# supply_test_2v1.net
KiCad netlist of a schematic drawn in EAGLE
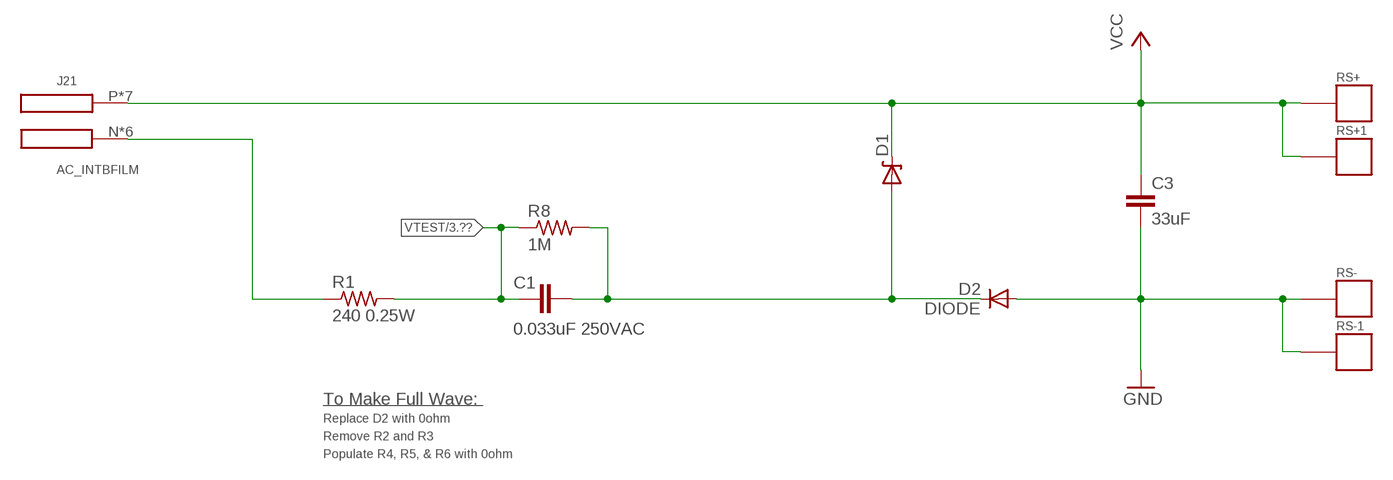
[diagram p0: schematic, sheet 1]
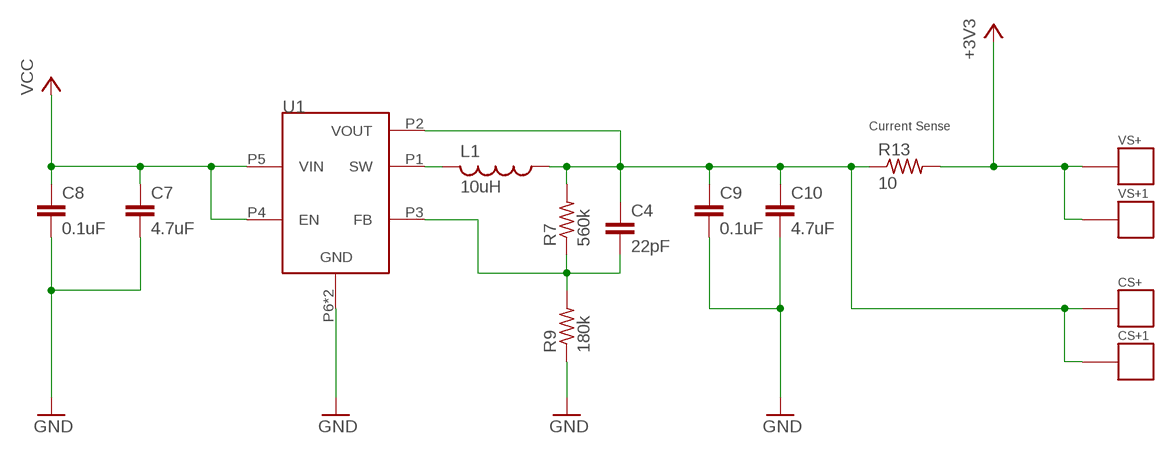
[diagram p1: schematic, sheet 2]
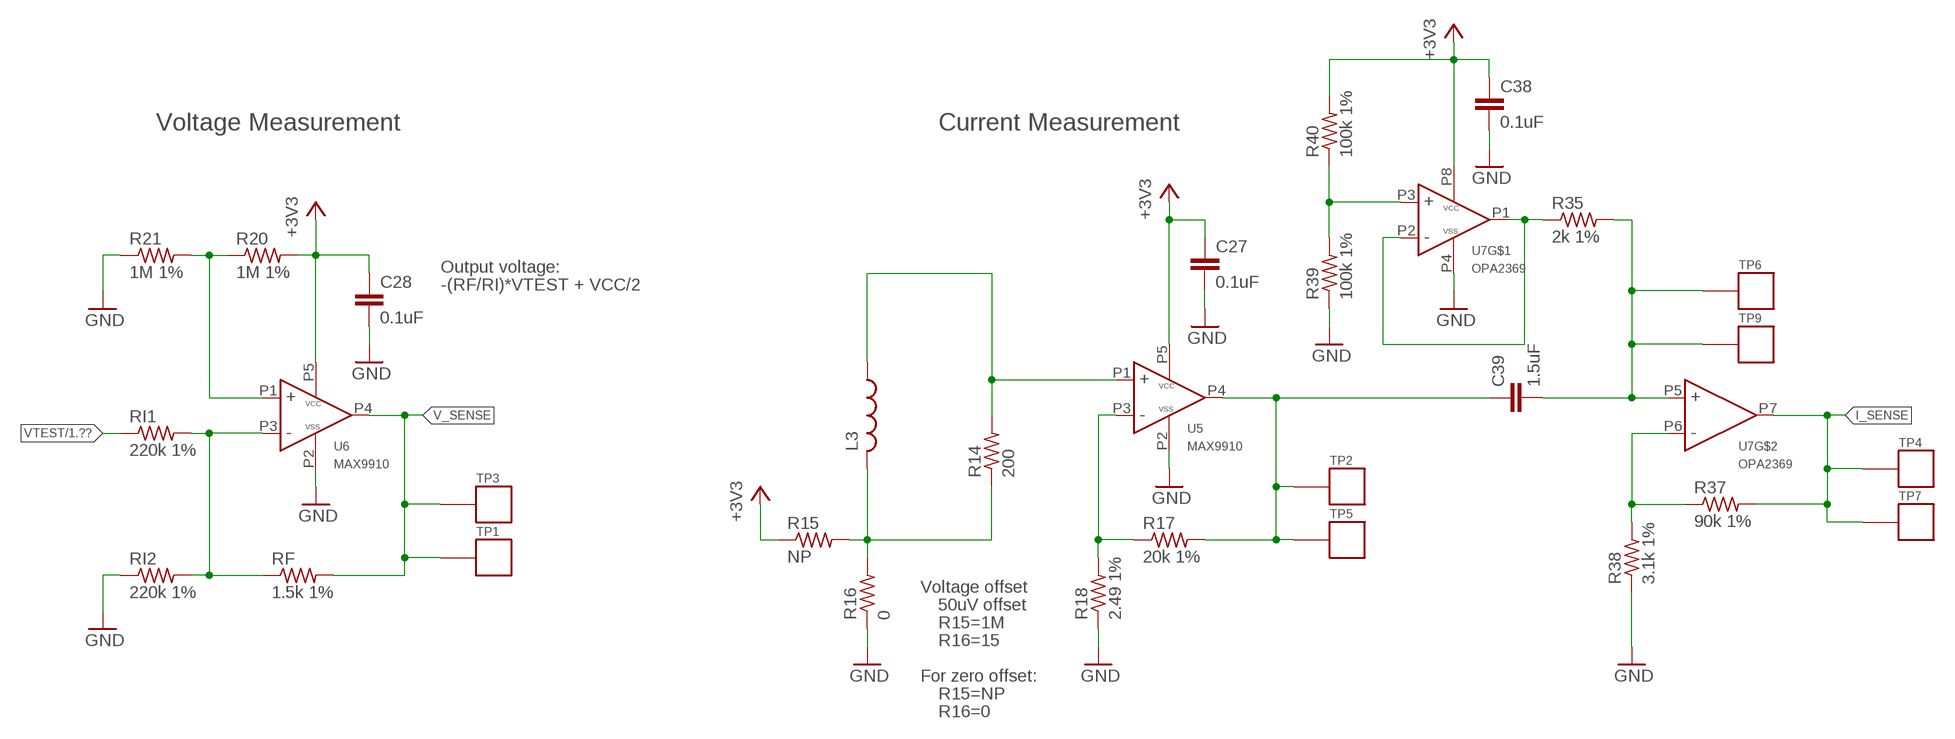
[diagram p2: schematic, sheet 3]

(export (version "E")
  (design (tool "Eeschema 10.0.6"))
  (components
    (comp (ref "C4")
      (value "22pF")
      (footprint "eagle-import:C0402")
      (libsource (lib "eagle-import") (part "C-EUC0402"))
    )
    (comp (ref "C7")
      (value "4.7uF")
      (footprint "eagle-import:C0402")
      (libsource (lib "eagle-import") (part "C-EUC0402"))
    )
    (comp (ref "C8")
      (value "0.1uF")
      (footprint "eagle-import:C0402")
      (libsource (lib "eagle-import") (part "C-EUC0402"))
    )
    (comp (ref "C9")
      (value "0.1uF")
      (footprint "eagle-import:C0402")
      (libsource (lib "eagle-import") (part "C-EUC0402"))
    )
    (comp (ref "C10")
      (value "4.7uF")
      (footprint "eagle-import:C0603")
      (libsource (lib "eagle-import") (part "C-EUC0603"))
    )
    (comp (ref "CS+")
      (value "TP_LONG")
      (footprint "eagle-import:TP_LONG")
      (libsource (lib "eagle-import") (part "TP_LONG"))
    )
    (comp (ref "CS+1")
      (value "TP_SMD")
      (footprint "eagle-import:TP_SMD")
      (libsource (lib "eagle-import") (part "TP_SMD"))
    )
    (comp (ref "L1")
      (value "10uH")
      (footprint "eagle-import:L0805")
      (libsource (lib "eagle-import") (part "L-USL0805"))
    )
    (comp (ref "R7")
      (value "560k")
      (footprint "eagle-import:R0402")
      (libsource (lib "eagle-import") (part "R-US_R0402"))
    )
    (comp (ref "R9")
      (value "180k")
      (footprint "eagle-import:R0402")
      (libsource (lib "eagle-import") (part "R-US_R0402"))
    )
    (comp (ref "R13")
      (value "10")
      (footprint "eagle-import:R0603")
      (libsource (lib "eagle-import") (part "R-US_R0603"))
    )
    (comp (ref "U1")
      (value "TPS62122")
      (footprint "eagle-import:WDFN-6")
      (libsource (lib "eagle-import") (part "TPS62122"))
    )
    (comp (ref "VS+")
      (value "TP_LONG")
      (footprint "eagle-import:TP_LONG")
      (libsource (lib "eagle-import") (part "TP_LONG"))
    )
    (comp (ref "VS+1")
      (value "TP_SMD")
      (footprint "eagle-import:TP_SMD")
      (libsource (lib "eagle-import") (part "TP_SMD"))
    )
    (comp (ref "C27")
      (value "0.1uF")
      (footprint "eagle-import:C0402")
      (libsource (lib "eagle-import") (part "C-EUC0402"))
    )
    (comp (ref "C28")
      (value "0.1uF")
      (footprint "eagle-import:C0402")
      (libsource (lib "eagle-import") (part "C-EUC0402"))
    )
    (comp (ref "C38")
      (value "0.1uF")
      (footprint "eagle-import:C0402")
      (libsource (lib "eagle-import") (part "C-EUC0402"))
    )
    (comp (ref "C39")
      (value "1.5uF")
      (footprint "eagle-import:C0402")
      (libsource (lib "eagle-import") (part "C-EUC0402"))
    )
    (comp (ref "L3")
      (value "L-USL0805")
      (footprint "eagle-import:L0805")
      (libsource (lib "eagle-import") (part "L-USL0805"))
    )
    (comp (ref "R14")
      (value "200")
      (footprint "eagle-import:R0402")
      (libsource (lib "eagle-import") (part "R-US_R0402"))
    )
    (comp (ref "R15")
      (value "NP")
      (footprint "eagle-import:R0402")
      (libsource (lib "eagle-import") (part "R-US_R0402"))
    )
    (comp (ref "R16")
      (value "0")
      (footprint "eagle-import:R0402")
      (libsource (lib "eagle-import") (part "R-US_R0402"))
    )
    (comp (ref "R17")
      (value "20k 1%")
      (footprint "eagle-import:R0402")
      (libsource (lib "eagle-import") (part "R-US_R0402"))
    )
    (comp (ref "R18")
      (value "2.49 1%")
      (footprint "eagle-import:R0402")
      (libsource (lib "eagle-import") (part "R-US_R0402"))
    )
    (comp (ref "R20")
      (value "1M 1%")
      (footprint "eagle-import:R0402")
      (libsource (lib "eagle-import") (part "R-US_R0402"))
    )
    (comp (ref "R21")
      (value "1M 1%")
      (footprint "eagle-import:R0402")
      (libsource (lib "eagle-import") (part "R-US_R0402"))
    )
    (comp (ref "R35")
      (value "2k 1%")
      (footprint "eagle-import:R0402")
      (libsource (lib "eagle-import") (part "R-US_R0402"))
    )
    (comp (ref "R37")
      (value "90k 1%")
      (footprint "eagle-import:R0402")
      (libsource (lib "eagle-import") (part "R-US_R0402"))
    )
    (comp (ref "R38")
      (value "3.1k 1%")
      (footprint "eagle-import:R0402")
      (libsource (lib "eagle-import") (part "R-US_R0402"))
    )
    (comp (ref "R39")
      (value "100k 1%")
      (footprint "eagle-import:R0402")
      (libsource (lib "eagle-import") (part "R-US_R0402"))
    )
    (comp (ref "R40")
      (value "100k 1%")
      (footprint "eagle-import:R0402")
      (libsource (lib "eagle-import") (part "R-US_R0402"))
    )
    (comp (ref "RF")
      (value "1.5k 1%")
      (footprint "eagle-import:R0402")
      (libsource (lib "eagle-import") (part "R-US_R0402"))
    )
    (comp (ref "RI1")
      (value "220k 1%")
      (footprint "eagle-import:R0402")
      (libsource (lib "eagle-import") (part "R-US_R0402"))
    )
    (comp (ref "RI2")
      (value "220k 1%")
      (footprint "eagle-import:R0402")
      (libsource (lib "eagle-import") (part "R-US_R0402"))
    )
    (comp (ref "TP1")
      (value "TP_SMD")
      (footprint "eagle-import:TP_SMD")
      (libsource (lib "eagle-import") (part "TP_SMD"))
    )
    (comp (ref "TP2")
      (value "TP_LONG")
      (footprint "eagle-import:TP_LONG")
      (libsource (lib "eagle-import") (part "TP_LONG"))
    )
    (comp (ref "TP3")
      (value "TP_LONG")
      (footprint "eagle-import:TP_LONG")
      (libsource (lib "eagle-import") (part "TP_LONG"))
    )
    (comp (ref "TP4")
      (value "TP_LONG")
      (footprint "eagle-import:TP_LONG")
      (libsource (lib "eagle-import") (part "TP_LONG"))
    )
    (comp (ref "TP5")
      (value "TP_SMD")
      (footprint "eagle-import:TP_SMD")
      (libsource (lib "eagle-import") (part "TP_SMD"))
    )
    (comp (ref "TP6")
      (value "TP_SMD")
      (footprint "eagle-import:TP_SMD")
      (libsource (lib "eagle-import") (part "TP_SMD"))
    )
    (comp (ref "TP7")
      (value "TP_SMD")
      (footprint "eagle-import:TP_SMD")
      (libsource (lib "eagle-import") (part "TP_SMD"))
    )
    (comp (ref "TP9")
      (value "TP_LONG")
      (footprint "eagle-import:TP_LONG")
      (libsource (lib "eagle-import") (part "TP_LONG"))
    )
    (comp (ref "U5")
      (value "MAX9910")
      (footprint "eagle-import:SC70-5")
      (libsource (lib "eagle-import") (part "MAX9910"))
    )
    (comp (ref "U6")
      (value "MAX9910")
      (footprint "eagle-import:SC70-5")
      (libsource (lib "eagle-import") (part "MAX9910"))
    )
    (comp (ref "U7")
      (value "OPA2369")
      (footprint "eagle-import:SOT-23-8")
      (libsource (lib "eagle-import") (part "OPA2369"))
    )
    (comp (ref "C1")
      (value "0.033uF 250VAC")
      (footprint "eagle-import:C2220-EDGE")
      (libsource (lib "eagle-import") (part "C-EUEDGE"))
    )
    (comp (ref "C3")
      (value "33uF")
      (footprint "eagle-import:C0603")
      (libsource (lib "eagle-import") (part "C-EUC0603"))
    )
    (comp (ref "D1")
      (value "ZENERBZT52")
      (footprint "eagle-import:BZT52")
      (fields (field (name "DIGIKEY") "BZT52C10T-7DICT-ND "))
      (libsource (lib "eagle-import") (part "ZENERBZT52"))
    )
    (comp (ref "D2")
      (value "DIODE")
      (footprint "eagle-import:BAS521")
      (libsource (lib "eagle-import") (part "DIODE"))
    )
    (comp (ref "J21")
      (value "AC_INTBFILM")
      (footprint "eagle-import:AC3_TBFILM")
      (libsource (lib "eagle-import") (part "AC_INTBFILM"))
    )
    (comp (ref "R1")
      (value "240 0.25W")
      (footprint "eagle-import:R0603")
      (libsource (lib "eagle-import") (part "R-US_R0603"))
    )
    (comp (ref "R8")
      (value "1M")
      (footprint "eagle-import:R0603")
      (libsource (lib "eagle-import") (part "R-US_R0603"))
    )
    (comp (ref "RS+")
      (value "TP_LONG")
      (footprint "eagle-import:TP_LONG")
      (libsource (lib "eagle-import") (part "TP_LONG"))
    )
    (comp (ref "RS+1")
      (value "TP_SMD")
      (footprint "eagle-import:TP_SMD")
      (libsource (lib "eagle-import") (part "TP_SMD"))
    )
    (comp (ref "RS-")
      (value "TP_LONG")
      (footprint "eagle-import:TP_LONG")
      (libsource (lib "eagle-import") (part "TP_LONG"))
    )
    (comp (ref "RS-1")
      (value "TP_SMD")
      (footprint "eagle-import:TP_SMD")
      (libsource (lib "eagle-import") (part "TP_SMD"))
    )
  )
  (nets
    (net (code "1") (name "+3V3") (class "Default")
      (node (ref "C27") (pin "1") (pinfunction "1_1") (pintype "passive"))
      (node (ref "C28") (pin "1") (pinfunction "1_1") (pintype "passive"))
      (node (ref "C38") (pin "1") (pinfunction "1_1") (pintype "passive"))
      (node (ref "R13") (pin "2") (pinfunction "2_2") (pintype "passive"))
      (node (ref "R15") (pin "1") (pinfunction "1_1") (pintype "passive"))
      (node (ref "R20") (pin "2") (pinfunction "2_2") (pintype "passive"))
      (node (ref "R40") (pin "2") (pinfunction "2_2") (pintype "passive"))
      (node (ref "U5") (pin "P5") (pinfunction "VCC_P5") (pintype "bidirectional"))
      (node (ref "U6") (pin "P5") (pinfunction "VCC_P5") (pintype "bidirectional"))
      (node (ref "U7") (pin "P8") (pinfunction "VCC_P8") (pintype "bidirectional"))
      (node (ref "VS+") (pin "P$1") (pinfunction "P$1_P$1") (pintype "bidirectional"))
      (node (ref "VS+1") (pin "P$1") (pinfunction "P$1_P$1") (pintype "bidirectional"))
    )
    (net (code "2") (name "GND") (class "Default")
      (node (ref "C10") (pin "2") (pinfunction "2_2") (pintype "passive"))
      (node (ref "C27") (pin "2") (pinfunction "2_2") (pintype "passive"))
      (node (ref "C28") (pin "2") (pinfunction "2_2") (pintype "passive"))
      (node (ref "C3") (pin "2") (pinfunction "2_2") (pintype "passive"))
      (node (ref "C38") (pin "2") (pinfunction "2_2") (pintype "passive"))
      (node (ref "C7") (pin "2") (pinfunction "2_2") (pintype "passive"))
      (node (ref "C8") (pin "2") (pinfunction "2_2") (pintype "passive"))
      (node (ref "C9") (pin "2") (pinfunction "2_2") (pintype "passive"))
      (node (ref "D2") (pin "A") (pinfunction "A_A") (pintype "passive"))
      (node (ref "R16") (pin "1") (pinfunction "1_1") (pintype "passive"))
      (node (ref "R18") (pin "1") (pinfunction "1_1") (pintype "passive"))
      (node (ref "R21") (pin "1") (pinfunction "1_1") (pintype "passive"))
      (node (ref "R38") (pin "1") (pinfunction "1_1") (pintype "passive"))
      (node (ref "R39") (pin "1") (pinfunction "1_1") (pintype "passive"))
      (node (ref "R9") (pin "1") (pinfunction "1_1") (pintype "passive"))
      (node (ref "RI2") (pin "1") (pinfunction "1_1") (pintype "passive"))
      (node (ref "RS-") (pin "P$1") (pinfunction "P$1_P$1") (pintype "bidirectional"))
      (node (ref "RS-1") (pin "P$1") (pinfunction "P$1_P$1") (pintype "bidirectional"))
      (node (ref "U1") (pin "P6") (pinfunction "GND_P6") (pintype "bidirectional"))
      (node (ref "U1") (pin "PAD") (pinfunction "GND_PAD") (pintype "bidirectional"))
      (node (ref "U5") (pin "P2") (pinfunction "VSS_P2") (pintype "bidirectional"))
      (node (ref "U6") (pin "P2") (pinfunction "VSS_P2") (pintype "bidirectional"))
      (node (ref "U7") (pin "P4") (pinfunction "VSS_P4") (pintype "bidirectional"))
    )
    (net (code "3") (name "I_SENSE") (class "Default")
      (node (ref "R37") (pin "2") (pinfunction "2_2") (pintype "passive"))
      (node (ref "TP4") (pin "P$1") (pinfunction "P$1_P$1") (pintype "bidirectional"))
      (node (ref "TP7") (pin "P$1") (pinfunction "P$1_P$1") (pintype "bidirectional"))
      (node (ref "U7") (pin "P7") (pinfunction "OUT_P7") (pintype "bidirectional"))
    )
    (net (code "4") (name "Net-(C1-Pad1)") (class "Default")
      (node (ref "C1") (pin "1") (pinfunction "1_1") (pintype "passive"))
      (node (ref "D1") (pin "A") (pinfunction "A_A") (pintype "passive"))
      (node (ref "D2") (pin "C") (pinfunction "C_C") (pintype "passive"))
      (node (ref "R8") (pin "2") (pinfunction "2_2") (pintype "passive"))
    )
    (net (code "5") (name "Net-(J21-N-PadN1)") (class "Default")
      (node (ref "J21") (pin "N") (pinfunction "N_N") (pintype "bidirectional"))
      (node (ref "J21") (pin "N1") (pinfunction "N_N1") (pintype "bidirectional"))
      (node (ref "J21") (pin "N2") (pinfunction "N_N2") (pintype "bidirectional"))
      (node (ref "J21") (pin "N3") (pinfunction "N_N3") (pintype "bidirectional"))
      (node (ref "J21") (pin "N4") (pinfunction "N_N4") (pintype "bidirectional"))
      (node (ref "J21") (pin "N5") (pinfunction "N_N5") (pintype "bidirectional"))
      (node (ref "R1") (pin "1") (pinfunction "1_1") (pintype "passive"))
    )
    (net (code "6") (name "Net-(L3-Pad2)") (class "Default")
      (node (ref "L3") (pin "2") (pinfunction "2_2") (pintype "passive"))
      (node (ref "R14") (pin "1") (pinfunction "1_1") (pintype "passive"))
      (node (ref "R15") (pin "2") (pinfunction "2_2") (pintype "passive"))
      (node (ref "R16") (pin "2") (pinfunction "2_2") (pintype "passive"))
    )
    (net (code "7") (name "Net-(U1-FB)") (class "Default")
      (node (ref "C4") (pin "2") (pinfunction "2_2") (pintype "passive"))
      (node (ref "R7") (pin "1") (pinfunction "1_1") (pintype "passive"))
      (node (ref "R9") (pin "2") (pinfunction "2_2") (pintype "passive"))
      (node (ref "U1") (pin "P3") (pinfunction "FB_P3") (pintype "bidirectional"))
    )
    (net (code "8") (name "Net-(U1-SW)") (class "Default")
      (node (ref "L1") (pin "2") (pinfunction "2_2") (pintype "passive"))
      (node (ref "U1") (pin "P1") (pinfunction "SW_P1") (pintype "bidirectional"))
    )
    (net (code "9") (name "Net-(U1-VOUT)") (class "Default")
      (node (ref "C10") (pin "1") (pinfunction "1_1") (pintype "passive"))
      (node (ref "C4") (pin "1") (pinfunction "1_1") (pintype "passive"))
      (node (ref "C9") (pin "1") (pinfunction "1_1") (pintype "passive"))
      (node (ref "CS+") (pin "P$1") (pinfunction "P$1_P$1") (pintype "bidirectional"))
      (node (ref "CS+1") (pin "P$1") (pinfunction "P$1_P$1") (pintype "bidirectional"))
      (node (ref "L1") (pin "1") (pinfunction "1_1") (pintype "passive"))
      (node (ref "R13") (pin "1") (pinfunction "1_1") (pintype "passive"))
      (node (ref "R7") (pin "2") (pinfunction "2_2") (pintype "passive"))
      (node (ref "U1") (pin "P2") (pinfunction "VOUT_P2") (pintype "bidirectional"))
    )
    (net (code "10") (name "Net-(U5-IN+)") (class "Default")
      (node (ref "L3") (pin "1") (pinfunction "1_1") (pintype "passive"))
      (node (ref "R14") (pin "2") (pinfunction "2_2") (pintype "passive"))
      (node (ref "U5") (pin "P1") (pinfunction "IN+_P1") (pintype "bidirectional"))
    )
    (net (code "11") (name "Net-(U5-IN-)") (class "Default")
      (node (ref "R17") (pin "1") (pinfunction "1_1") (pintype "passive"))
      (node (ref "R18") (pin "2") (pinfunction "2_2") (pintype "passive"))
      (node (ref "U5") (pin "P3") (pinfunction "IN-_P3") (pintype "bidirectional"))
    )
    (net (code "12") (name "Net-(U5-OUT)") (class "Default")
      (node (ref "C39") (pin "1") (pinfunction "1_1") (pintype "passive"))
      (node (ref "R17") (pin "2") (pinfunction "2_2") (pintype "passive"))
      (node (ref "TP2") (pin "P$1") (pinfunction "P$1_P$1") (pintype "bidirectional"))
      (node (ref "TP5") (pin "P$1") (pinfunction "P$1_P$1") (pintype "bidirectional"))
      (node (ref "U5") (pin "P4") (pinfunction "OUT_P4") (pintype "bidirectional"))
    )
    (net (code "13") (name "Net-(U6-IN+)") (class "Default")
      (node (ref "R20") (pin "1") (pinfunction "1_1") (pintype "passive"))
      (node (ref "R21") (pin "2") (pinfunction "2_2") (pintype "passive"))
      (node (ref "U6") (pin "P1") (pinfunction "IN+_P1") (pintype "bidirectional"))
    )
    (net (code "14") (name "Net-(U6-IN-)") (class "Default")
      (node (ref "RF") (pin "1") (pinfunction "1_1") (pintype "passive"))
      (node (ref "RI1") (pin "2") (pinfunction "2_2") (pintype "passive"))
      (node (ref "RI2") (pin "2") (pinfunction "2_2") (pintype "passive"))
      (node (ref "U6") (pin "P3") (pinfunction "IN-_P3") (pintype "bidirectional"))
    )
    (net (code "15") (name "Net-(U7A-IN+)") (class "Default")
      (node (ref "R39") (pin "2") (pinfunction "2_2") (pintype "passive"))
      (node (ref "R40") (pin "1") (pinfunction "1_1") (pintype "passive"))
      (node (ref "U7") (pin "P3") (pinfunction "IN+_P3") (pintype "bidirectional"))
    )
    (net (code "16") (name "Net-(U7A-IN-)") (class "Default")
      (node (ref "R35") (pin "1") (pinfunction "1_1") (pintype "passive"))
      (node (ref "U7") (pin "P1") (pinfunction "OUT_P1") (pintype "bidirectional"))
      (node (ref "U7") (pin "P2") (pinfunction "IN-_P2") (pintype "bidirectional"))
    )
    (net (code "17") (name "Net-(U7B-IN+)") (class "Default")
      (node (ref "C39") (pin "2") (pinfunction "2_2") (pintype "passive"))
      (node (ref "R35") (pin "2") (pinfunction "2_2") (pintype "passive"))
      (node (ref "TP6") (pin "P$1") (pinfunction "P$1_P$1") (pintype "bidirectional"))
      (node (ref "TP9") (pin "P$1") (pinfunction "P$1_P$1") (pintype "bidirectional"))
      (node (ref "U7") (pin "P5") (pinfunction "IN+_P5") (pintype "bidirectional"))
    )
    (net (code "18") (name "Net-(U7B-IN-)") (class "Default")
      (node (ref "R37") (pin "1") (pinfunction "1_1") (pintype "passive"))
      (node (ref "R38") (pin "2") (pinfunction "2_2") (pintype "passive"))
      (node (ref "U7") (pin "P6") (pinfunction "IN-_P6") (pintype "bidirectional"))
    )
    (net (code "19") (name "VCC") (class "Default")
      (node (ref "C3") (pin "1") (pinfunction "1_1") (pintype "passive"))
      (node (ref "C7") (pin "1") (pinfunction "1_1") (pintype "passive"))
      (node (ref "C8") (pin "1") (pinfunction "1_1") (pintype "passive"))
      (node (ref "D1") (pin "C") (pinfunction "C_C") (pintype "passive"))
      (node (ref "J21") (pin "P") (pinfunction "P_P") (pintype "bidirectional"))
      (node (ref "J21") (pin "P1") (pinfunction "P_P1") (pintype "bidirectional"))
      (node (ref "J21") (pin "P2") (pinfunction "P_P2") (pintype "bidirectional"))
      (node (ref "J21") (pin "P3") (pinfunction "P_P3") (pintype "bidirectional"))
      (node (ref "J21") (pin "P4") (pinfunction "P_P4") (pintype "bidirectional"))
      (node (ref "J21") (pin "P5") (pinfunction "P_P5") (pintype "bidirectional"))
      (node (ref "J21") (pin "P6") (pinfunction "P_P6") (pintype "bidirectional"))
      (node (ref "RS+") (pin "P$1") (pinfunction "P$1_P$1") (pintype "bidirectional"))
      (node (ref "RS+1") (pin "P$1") (pinfunction "P$1_P$1") (pintype "bidirectional"))
      (node (ref "U1") (pin "P4") (pinfunction "EN_P4") (pintype "bidirectional"))
      (node (ref "U1") (pin "P5") (pinfunction "VIN_P5") (pintype "bidirectional"))
    )
    (net (code "20") (name "VTEST") (class "Default")
      (node (ref "C1") (pin "2") (pinfunction "2_2") (pintype "passive"))
      (node (ref "R1") (pin "2") (pinfunction "2_2") (pintype "passive"))
      (node (ref "R8") (pin "1") (pinfunction "1_1") (pintype "passive"))
      (node (ref "RI1") (pin "1") (pinfunction "1_1") (pintype "passive"))
    )
    (net (code "21") (name "V_SENSE") (class "Default")
      (node (ref "RF") (pin "2") (pinfunction "2_2") (pintype "passive"))
      (node (ref "TP1") (pin "P$1") (pinfunction "P$1_P$1") (pintype "bidirectional"))
      (node (ref "TP3") (pin "P$1") (pinfunction "P$1_P$1") (pintype "bidirectional"))
      (node (ref "U6") (pin "P4") (pinfunction "OUT_P4") (pintype "bidirectional"))
    )
  )
)
